# Motor_3.net
KiCad netlist of a schematic drawn in Altium Designer
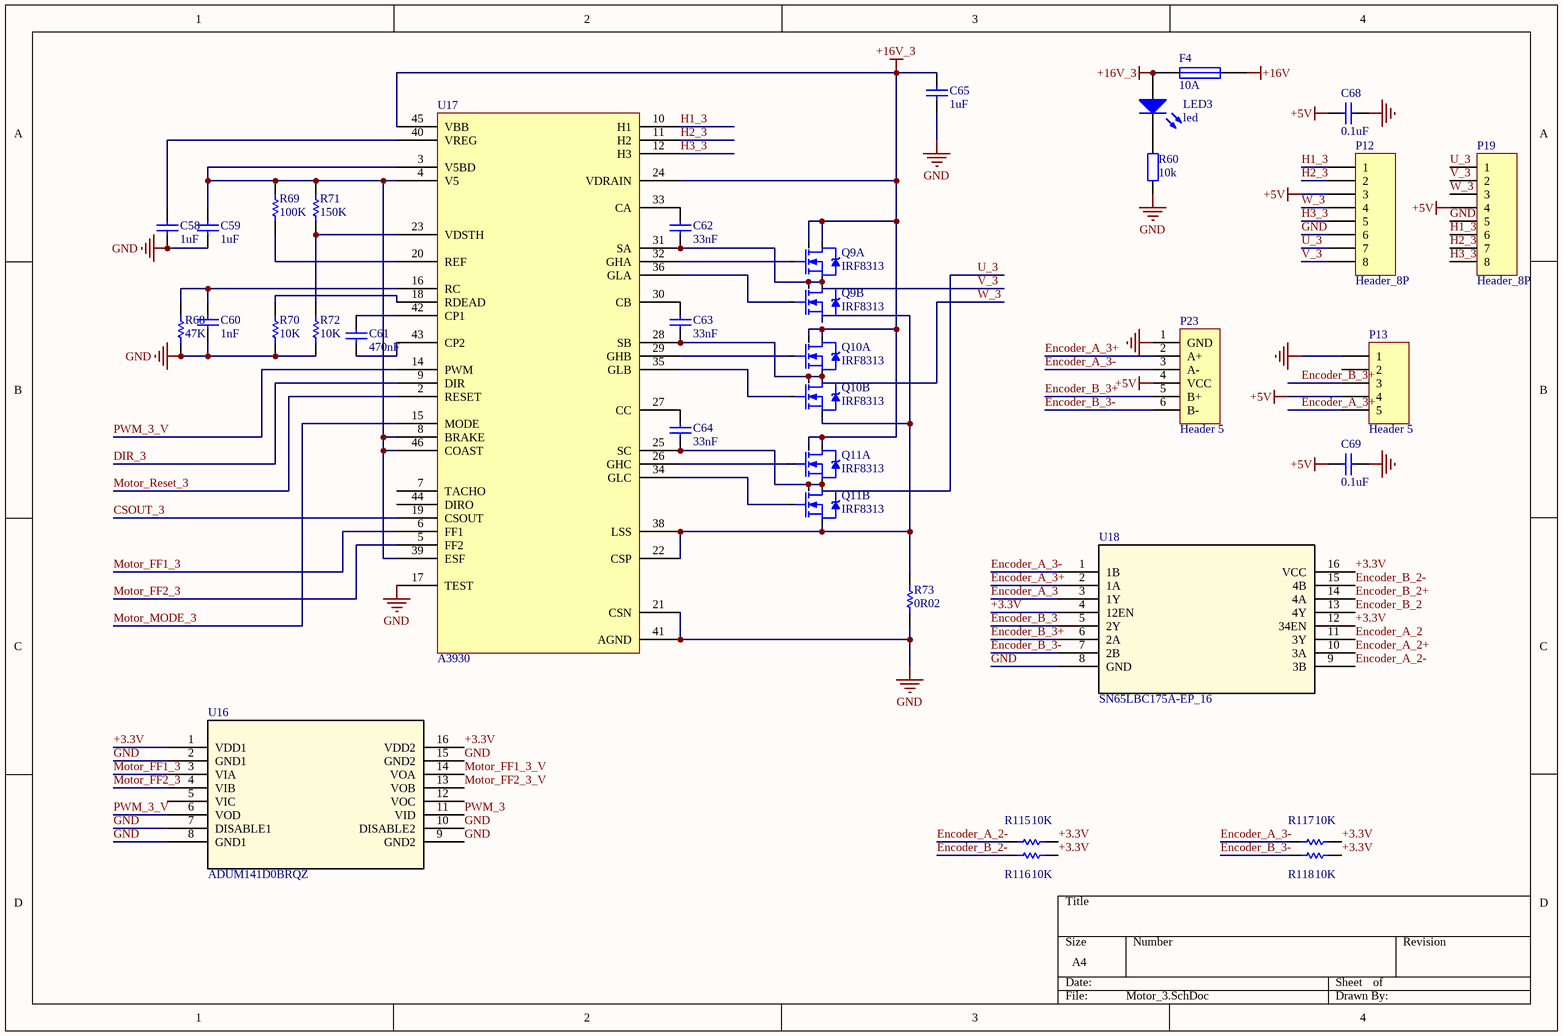
[diagram p0: Motor_3.SchDoc]

(export (version "E")
  (design (tool "Eeschema 10.0.6"))
  (components
    (comp (ref "C58")
      (value "1uF")
      (footprint "0603C")
      (description "Capacitor")
      (fields
        (field (name "MANUFACTURER") "Generic Components")
        (field (name "Comment") "1uf")
        (field (name "PUBLISHER") "Altium Hobart Technology Centre")
      )
      (libsource (lib "hp_2018_03") (part "Cap"))
    )
    (comp (ref "C59")
      (value "1uF")
      (footprint "0603C")
      (description "Capacitor")
      (fields
        (field (name "MANUFACTURER") "Generic Components")
        (field (name "Comment") "1uf")
        (field (name "PUBLISHER") "Altium Hobart Technology Centre")
      )
      (libsource (lib "hp_2018_03") (part "Cap"))
    )
    (comp (ref "C60")
      (value "1nF")
      (footprint "0603C")
      (description "Capacitor")
      (fields
        (field (name "MANUFACTURER") "Generic Components")
        (field (name "Comment") "1nf")
        (field (name "PUBLISHER") "Altium Hobart Technology Centre")
      )
      (libsource (lib "hp_2018_03") (part "Cap"))
    )
    (comp (ref "C61")
      (value "470nF")
      (footprint "0603C")
      (description "Capacitor")
      (fields
        (field (name "MANUFACTURER") "Generic Components")
        (field (name "Comment") "470nf")
        (field (name "PUBLISHER") "Altium Hobart Technology Centre")
      )
      (libsource (lib "hp_2018_03") (part "Cap"))
    )
    (comp (ref "C62")
      (value "33nF")
      (footprint "0603C")
      (description "Capacitor")
      (fields
        (field (name "MANUFACTURER") "Generic Components")
        (field (name "Comment") "33nf")
        (field (name "PUBLISHER") "Altium Hobart Technology Centre")
      )
      (libsource (lib "hp_2018_03") (part "Cap"))
    )
    (comp (ref "C63")
      (value "33nF")
      (footprint "0603C")
      (description "Capacitor")
      (fields
        (field (name "MANUFACTURER") "Generic Components")
        (field (name "Comment") "33nf")
        (field (name "PUBLISHER") "Altium Hobart Technology Centre")
      )
      (libsource (lib "hp_2018_03") (part "Cap"))
    )
    (comp (ref "C64")
      (value "33nF")
      (footprint "0603C")
      (description "Capacitor")
      (fields
        (field (name "MANUFACTURER") "Generic Components")
        (field (name "Comment") "33nf")
        (field (name "PUBLISHER") "Altium Hobart Technology Centre")
      )
      (libsource (lib "hp_2018_03") (part "Cap"))
    )
    (comp (ref "C65")
      (value "1uF")
      (footprint "0603C")
      (description "Capacitor")
      (fields
        (field (name "MANUFACTURER") "Generic Components")
        (field (name "Comment") "1uf")
        (field (name "PUBLISHER") "Altium Hobart Technology Centre")
      )
      (libsource (lib "hp_2018_03") (part "Cap"))
    )
    (comp (ref "C68")
      (value "0.1uF")
      (footprint "0603C")
      (description "Capacitor")
      (fields
        (field (name "MANUFACTURER") "Generic Components")
        (field (name "Comment") "0.1uf")
        (field (name "PUBLISHER") "Altium Hobart Technology Centre")
      )
      (libsource (lib "hp_2018_03") (part "Cap"))
    )
    (comp (ref "C69")
      (value "0.1uF")
      (footprint "0603C")
      (description "Capacitor")
      (fields
        (field (name "MANUFACTURER") "Generic Components")
        (field (name "Comment") "0.1uf")
        (field (name "PUBLISHER") "Altium Hobart Technology Centre")
      )
      (libsource (lib "hp_2018_03") (part "Cap"))
    )
    (comp (ref "F4")
      (value "10A")
      (footprint "Main_Board:FUSE_HEADER")
      (libsource (lib "Integrated_Library2") (part "FUSE"))
    )
    (comp (ref "LED3")
      (value "led")
      (footprint "0603_diode")
      (libsource (lib "Integrated_Library2") (part "led"))
    )
    (comp (ref "P12")
      (value "Header_8P")
      (footprint "8P - WF25122")
      (description "Used for Motor connection in ZJUNlict")
      (libsource (lib "Integrated_Library2") (part "Header_8P"))
    )
    (comp (ref "P13")
      (value "Header 5")
      (footprint "SHDR5")
      (description "Header, 5-Pin")
      (fields (field (name "PUBLISHER") "Altium Limited"))
      (libsource (lib "Miscellaneous Connectors") (part "Header 5"))
    )
    (comp (ref "P19")
      (value "Header_8P")
      (footprint "SHDR8")
      (description "Used for Motor connection in ZJUNlict")
      (libsource (lib "Integrated_Library2") (part "Header_8P"))
    )
    (comp (ref "P23")
      (value "Header 5")
      (footprint "SHDR6")
      (description "Header, 5-Pin")
      (fields (field (name "PUBLISHER") "Altium Limited"))
      (libsource (lib "Main_Board") (part "Header 6"))
    )
    (comp (ref "Q9") (value "IRF8313") (footprint "so-8 bg") (libsource (lib "BLDC") (part "SO-8 IRF8313")))
    (comp (ref "Q10") (value "IRF8313") (footprint "so-8 bg") (libsource (lib "BLDC") (part "SO-8 IRF8313")))
    (comp (ref "Q11") (value "IRF8313") (footprint "so-8 bg") (libsource (lib "BLDC") (part "SO-8 IRF8313")))
    (comp (ref "R60") (value "10k") (footprint "0603") (libsource (lib "Integrated_Library2") (part "res")))
    (comp (ref "R68")
      (value "47K")
      (footprint "0603R")
      (description "Resistor")
      (fields
        (field (name "MANUFACTURER") "Generic Components")
        (field (name "Comment") "47k")
        (field (name "PUBLISHER") "Altium Hobart Technology Centre")
      )
      (libsource (lib "hp_2018_03") (part "Res1"))
    )
    (comp (ref "R69")
      (value "100K")
      (footprint "0603R")
      (description "Resistor")
      (fields
        (field (name "MANUFACTURER") "Generic Components")
        (field (name "Comment") "100k")
        (field (name "PUBLISHER") "Altium Hobart Technology Centre")
      )
      (libsource (lib "hp_2018_03") (part "Res1"))
    )
    (comp (ref "R70")
      (value "10K")
      (footprint "0603R")
      (description "Resistor")
      (fields
        (field (name "MANUFACTURER") "Generic Components")
        (field (name "Comment") "10k")
        (field (name "PUBLISHER") "Altium Hobart Technology Centre")
      )
      (libsource (lib "hp_2018_03") (part "Res1"))
    )
    (comp (ref "R71")
      (value "150K")
      (footprint "0603R")
      (description "Resistor")
      (fields
        (field (name "MANUFACTURER") "Generic Components")
        (field (name "Comment") "100k")
        (field (name "PUBLISHER") "Altium Hobart Technology Centre")
      )
      (libsource (lib "hp_2018_03") (part "Res1"))
    )
    (comp (ref "R72")
      (value "10K")
      (footprint "0603R")
      (description "Resistor")
      (fields
        (field (name "MANUFACTURER") "Generic Components")
        (field (name "Comment") "10k")
        (field (name "PUBLISHER") "Altium Hobart Technology Centre")
      )
      (libsource (lib "hp_2018_03") (part "Res1"))
    )
    (comp (ref "R73")
      (value "0R02")
      (footprint "1206 10A")
      (description "Resistor")
      (fields
        (field (name "MANUFACTURER") "Generic Components")
        (field (name "Comment") "0.02")
        (field (name "PUBLISHER") "Altium Hobart Technology Centre")
      )
      (libsource (lib "hp_2018_03") (part "Res1"))
    )
    (comp (ref "R115")
      (value "10K")
      (footprint "0603R")
      (description "Resistor")
      (fields
        (field (name "MANUFACTURER") "Generic Components")
        (field (name "Comment") "10k")
        (field (name "PUBLISHER") "Altium Hobart Technology Centre")
      )
      (libsource (lib "hp_2018_03") (part "Res1"))
    )
    (comp (ref "R116")
      (value "10K")
      (footprint "0603R")
      (description "Resistor")
      (fields
        (field (name "MANUFACTURER") "Generic Components")
        (field (name "Comment") "10k")
        (field (name "PUBLISHER") "Altium Hobart Technology Centre")
      )
      (libsource (lib "hp_2018_03") (part "Res1"))
    )
    (comp (ref "R117")
      (value "10K")
      (footprint "0603R")
      (description "Resistor")
      (fields
        (field (name "MANUFACTURER") "Generic Components")
        (field (name "Comment") "10k")
        (field (name "PUBLISHER") "Altium Hobart Technology Centre")
      )
      (libsource (lib "hp_2018_03") (part "Res1"))
    )
    (comp (ref "R118")
      (value "10K")
      (footprint "0603R")
      (description "Resistor")
      (fields
        (field (name "MANUFACTURER") "Generic Components")
        (field (name "Comment") "10k")
        (field (name "PUBLISHER") "Altium Hobart Technology Centre")
      )
      (libsource (lib "hp_2018_03") (part "Res1"))
    )
    (comp (ref "U16")
      (value "ADUM141D0BRQZ")
      (footprint "Main_Board:RQ_16")
      (description "Imported")
      (libsource (lib "Main_Board") (part "ADUM141D0BRQZ"))
    )
    (comp (ref "U17") (value "A3930") (footprint "LQFP-48") (libsource (lib "BLDC") (part "LQFP 48")))
    (comp (ref "U18")
      (value "SN65LBC175A-EP_16")
      (footprint "SOP16")
      (description "Quadruple 2-Input Positive-NAND Gates")
      (fields
        (field (name "MANUFACTURER") "Texas Instruments")
        (field (name "GENERIC_PART_NUMBER") "74AC11000")
      )
      (libsource (lib "Main_Board") (part "SN65LBC175A-EP_16"))
    )
  )
  (nets
    (net (code "1") (name "+5V") (class "Default")
      (node (ref "C68") (pin "2") (pinfunction "2_2") (pintype "passive"))
      (node (ref "C69") (pin "2") (pinfunction "2_2") (pintype "passive"))
      (node (ref "P12") (pin "3") (pinfunction "3_3") (pintype "passive"))
      (node (ref "P13") (pin "4") (pinfunction "4_4") (pintype "passive"))
      (node (ref "P19") (pin "4") (pinfunction "4_4") (pintype "passive"))
      (node (ref "P23") (pin "4") (pinfunction "VCC_4") (pintype "passive"))
    )
    (net (code "2") (name "+16V") (class "Default")
      (node (ref "F4") (pin "1") (pinfunction "1_1") (pintype "passive"))
    )
    (net (code "3") (name "+16V_3") (class "Default")
      (node (ref "C65") (pin "2") (pinfunction "2_2") (pintype "passive"))
      (node (ref "F4") (pin "2") (pinfunction "2_2") (pintype "passive"))
      (node (ref "LED3") (pin "1") (pinfunction "A_1") (pintype "passive"))
      (node (ref "Q10") (pin "7") (pinfunction "D2_7") (pintype "passive"))
      (node (ref "Q10") (pin "8") (pinfunction "D2_8") (pintype "passive"))
      (node (ref "Q11") (pin "7") (pinfunction "D2_7") (pintype "passive"))
      (node (ref "Q11") (pin "8") (pinfunction "D2_8") (pintype "passive"))
      (node (ref "Q9") (pin "7") (pinfunction "D2_7") (pintype "passive"))
      (node (ref "Q9") (pin "8") (pinfunction "D2_8") (pintype "passive"))
      (node (ref "U17") (pin "24") (pinfunction "VDRAIN_24") (pintype "passive"))
      (node (ref "U17") (pin "45") (pinfunction "VBB_45") (pintype "passive"))
    )
    (net (code "4") (name "/+3.3V") (class "Default")
      (node (ref "R115") (pin "1") (pinfunction "1_1") (pintype "passive"))
      (node (ref "R116") (pin "1") (pinfunction "1_1") (pintype "passive"))
      (node (ref "R117") (pin "1") (pinfunction "1_1") (pintype "passive"))
      (node (ref "R118") (pin "1") (pinfunction "1_1") (pintype "passive"))
      (node (ref "U16") (pin "1") (pinfunction "VDD1_1") (pintype "passive"))
      (node (ref "U16") (pin "16") (pinfunction "VDD2_16") (pintype "passive"))
      (node (ref "U18") (pin "12") (pinfunction "34EN_12") (pintype "passive"))
      (node (ref "U18") (pin "16") (pinfunction "VCC_16") (pintype "power_in"))
      (node (ref "U18") (pin "4") (pinfunction "12EN_4") (pintype "passive"))
    )
    (net (code "5") (name "/CSOUT_3") (class "Default")
      (node (ref "U17") (pin "19") (pinfunction "CSOUT_19") (pintype "passive"))
    )
    (net (code "6") (name "/DIR_3") (class "Default")
      (node (ref "U17") (pin "9") (pinfunction "DIR_9") (pintype "passive"))
    )
    (net (code "7") (name "/Encoder_A_2") (class "Default")
      (node (ref "U18") (pin "11") (pinfunction "3Y_11") (pintype "passive"))
    )
    (net (code "8") (name "/Encoder_A_2+") (class "Default")
      (node (ref "U18") (pin "10") (pinfunction "3A_10") (pintype "passive"))
    )
    (net (code "9") (name "/Encoder_A_2-") (class "Default")
      (node (ref "R115") (pin "2") (pinfunction "2_2") (pintype "passive"))
      (node (ref "U18") (pin "9") (pinfunction "3B_9") (pintype "passive"))
    )
    (net (code "10") (name "/Encoder_A_3") (class "Default")
      (node (ref "U18") (pin "3") (pinfunction "1Y_3") (pintype "passive"))
    )
    (net (code "11") (name "/Encoder_A_3+") (class "Default")
      (node (ref "P13") (pin "5") (pinfunction "5_5") (pintype "passive"))
      (node (ref "P23") (pin "2") (pinfunction "A+_2") (pintype "passive"))
      (node (ref "U18") (pin "2") (pinfunction "1A_2") (pintype "passive"))
    )
    (net (code "12") (name "/Encoder_A_3-") (class "Default")
      (node (ref "P23") (pin "3") (pinfunction "A-_3") (pintype "passive"))
      (node (ref "R117") (pin "2") (pinfunction "2_2") (pintype "passive"))
      (node (ref "U18") (pin "1") (pinfunction "1B_1") (pintype "passive"))
    )
    (net (code "13") (name "/Encoder_B_2") (class "Default")
      (node (ref "U18") (pin "13") (pinfunction "4Y_13") (pintype "passive"))
    )
    (net (code "14") (name "/Encoder_B_2+") (class "Default")
      (node (ref "U18") (pin "14") (pinfunction "4A_14") (pintype "passive"))
    )
    (net (code "15") (name "/Encoder_B_2-") (class "Default")
      (node (ref "R116") (pin "2") (pinfunction "2_2") (pintype "passive"))
      (node (ref "U18") (pin "15") (pinfunction "4B_15") (pintype "passive"))
    )
    (net (code "16") (name "/Encoder_B_3") (class "Default")
      (node (ref "U18") (pin "5") (pinfunction "2Y_5") (pintype "passive"))
    )
    (net (code "17") (name "/Encoder_B_3+") (class "Default")
      (node (ref "P13") (pin "3") (pinfunction "3_3") (pintype "passive"))
      (node (ref "P23") (pin "5") (pinfunction "B+_5") (pintype "passive"))
      (node (ref "U18") (pin "6") (pinfunction "2A_6") (pintype "passive"))
    )
    (net (code "18") (name "/Encoder_B_3-") (class "Default")
      (node (ref "P23") (pin "6") (pinfunction "B-_6") (pintype "passive"))
      (node (ref "R118") (pin "2") (pinfunction "2_2") (pintype "passive"))
      (node (ref "U18") (pin "7") (pinfunction "2B_7") (pintype "passive"))
    )
    (net (code "19") (name "/H1_3") (class "Default")
      (node (ref "P12") (pin "1") (pinfunction "1_1") (pintype "passive"))
      (node (ref "P19") (pin "6") (pinfunction "6_6") (pintype "passive"))
      (node (ref "U17") (pin "10") (pinfunction "H1_10") (pintype "passive"))
    )
    (net (code "20") (name "/H2_3") (class "Default")
      (node (ref "P12") (pin "2") (pinfunction "2_2") (pintype "passive"))
      (node (ref "P19") (pin "7") (pinfunction "7_7") (pintype "passive"))
      (node (ref "U17") (pin "11") (pinfunction "H2_11") (pintype "passive"))
    )
    (net (code "21") (name "/H3_3") (class "Default")
      (node (ref "P12") (pin "5") (pinfunction "5_5") (pintype "passive"))
      (node (ref "P19") (pin "8") (pinfunction "8_8") (pintype "passive"))
      (node (ref "U17") (pin "12") (pinfunction "H3_12") (pintype "passive"))
    )
    (net (code "22") (name "/Motor_FF1_3") (class "Default")
      (node (ref "U16") (pin "3") (pinfunction "VIA_3") (pintype "passive"))
      (node (ref "U17") (pin "6") (pinfunction "FF1_6") (pintype "passive"))
    )
    (net (code "23") (name "/Motor_FF1_3_V") (class "Default")
      (node (ref "U16") (pin "14") (pinfunction "VOA_14") (pintype "passive"))
    )
    (net (code "24") (name "/Motor_FF2_3") (class "Default")
      (node (ref "U16") (pin "4") (pinfunction "VIB_4") (pintype "passive"))
      (node (ref "U17") (pin "5") (pinfunction "FF2_5") (pintype "passive"))
    )
    (net (code "25") (name "/Motor_FF2_3_V") (class "Default")
      (node (ref "U16") (pin "13") (pinfunction "VOB_13") (pintype "passive"))
    )
    (net (code "26") (name "/Motor_MODE_3") (class "Default")
      (node (ref "U17") (pin "15") (pinfunction "MODE_15") (pintype "passive"))
    )
    (net (code "27") (name "/Motor_Reset_3") (class "Default")
      (node (ref "U17") (pin "2") (pinfunction "RESET_2") (pintype "passive"))
    )
    (net (code "28") (name "/PWM_3") (class "Default")
      (node (ref "U16") (pin "11") (pinfunction "VID_11") (pintype "passive"))
    )
    (net (code "29") (name "/PWM_3_V") (class "Default")
      (node (ref "U16") (pin "6") (pinfunction "VOD_6") (pintype "passive"))
      (node (ref "U17") (pin "14") (pinfunction "PWM_14") (pintype "passive"))
    )
    (net (code "30") (name "/U_3") (class "Default")
      (node (ref "C64") (pin "1") (pinfunction "1_1") (pintype "passive"))
      (node (ref "P12") (pin "7") (pinfunction "7_7") (pintype "passive"))
      (node (ref "P19") (pin "1") (pinfunction "1_1") (pintype "passive"))
      (node (ref "Q11") (pin "1") (pinfunction "S2_1") (pintype "passive"))
      (node (ref "Q11") (pin "5") (pinfunction "D1_5") (pintype "passive"))
      (node (ref "Q11") (pin "6") (pinfunction "D1_6") (pintype "passive"))
      (node (ref "U17") (pin "25") (pinfunction "SC_25") (pintype "passive"))
    )
    (net (code "31") (name "/V_3") (class "Default")
      (node (ref "C62") (pin "1") (pinfunction "1_1") (pintype "passive"))
      (node (ref "P12") (pin "8") (pinfunction "8_8") (pintype "passive"))
      (node (ref "P19") (pin "2") (pinfunction "2_2") (pintype "passive"))
      (node (ref "Q9") (pin "1") (pinfunction "S2_1") (pintype "passive"))
      (node (ref "Q9") (pin "5") (pinfunction "D1_5") (pintype "passive"))
      (node (ref "Q9") (pin "6") (pinfunction "D1_6") (pintype "passive"))
      (node (ref "U17") (pin "31") (pinfunction "SA_31") (pintype "passive"))
    )
    (net (code "32") (name "/W_3") (class "Default")
      (node (ref "C63") (pin "1") (pinfunction "1_1") (pintype "passive"))
      (node (ref "P12") (pin "4") (pinfunction "4_4") (pintype "passive"))
      (node (ref "P19") (pin "3") (pinfunction "3_3") (pintype "passive"))
      (node (ref "Q10") (pin "1") (pinfunction "S2_1") (pintype "passive"))
      (node (ref "Q10") (pin "5") (pinfunction "D1_5") (pintype "passive"))
      (node (ref "Q10") (pin "6") (pinfunction "D1_6") (pintype "passive"))
      (node (ref "U17") (pin "28") (pinfunction "SB_28") (pintype "passive"))
    )
    (net (code "33") (name "GND") (class "Default")
      (node (ref "C58") (pin "1") (pinfunction "1_1") (pintype "passive"))
      (node (ref "C59") (pin "1") (pinfunction "1_1") (pintype "passive"))
      (node (ref "C60") (pin "1") (pinfunction "1_1") (pintype "passive"))
      (node (ref "C65") (pin "1") (pinfunction "1_1") (pintype "passive"))
      (node (ref "C68") (pin "1") (pinfunction "1_1") (pintype "passive"))
      (node (ref "C69") (pin "1") (pinfunction "1_1") (pintype "passive"))
      (node (ref "P12") (pin "6") (pinfunction "6_6") (pintype "passive"))
      (node (ref "P13") (pin "1") (pinfunction "1_1") (pintype "passive"))
      (node (ref "P19") (pin "5") (pinfunction "5_5") (pintype "passive"))
      (node (ref "P23") (pin "1") (pinfunction "GND_1") (pintype "passive"))
      (node (ref "R60") (pin "1") (pinfunction "1_1") (pintype "passive"))
      (node (ref "R68") (pin "1") (pinfunction "1_1") (pintype "passive"))
      (node (ref "R70") (pin "1") (pinfunction "1_1") (pintype "passive"))
      (node (ref "R72") (pin "1") (pinfunction "1_1") (pintype "passive"))
      (node (ref "R73") (pin "1") (pinfunction "1_1") (pintype "passive"))
      (node (ref "U16") (pin "10") (pinfunction "DISABLE2_10") (pintype "passive"))
      (node (ref "U16") (pin "15") (pinfunction "GND2_15") (pintype "passive"))
      (node (ref "U16") (pin "2") (pinfunction "GND1_2") (pintype "passive"))
      (node (ref "U16") (pin "7") (pinfunction "DISABLE1_7") (pintype "passive"))
      (node (ref "U16") (pin "8") (pinfunction "GND1_8") (pintype "passive"))
      (node (ref "U16") (pin "9") (pinfunction "GND2_9") (pintype "passive"))
      (node (ref "U17") (pin "17") (pinfunction "TEST_17") (pintype "passive"))
      (node (ref "U17") (pin "21") (pinfunction "CSN_21") (pintype "passive"))
      (node (ref "U17") (pin "41") (pinfunction "AGND_41") (pintype "passive"))
      (node (ref "U18") (pin "8") (pinfunction "GND_8") (pintype "passive"))
    )
    (net (code "34") (name "Net-(LED3-K)") (class "Default")
      (node (ref "LED3") (pin "2") (pinfunction "K_2") (pintype "passive"))
      (node (ref "R60") (pin "2") (pinfunction "2_2") (pintype "passive"))
    )
    (net (code "35") (name "Net-(Q9A-G2)") (class "Default")
      (node (ref "Q9") (pin "2") (pinfunction "G2_2") (pintype "passive"))
      (node (ref "U17") (pin "32") (pinfunction "GHA_32") (pintype "passive"))
    )
    (net (code "36") (name "Net-(Q9B-G1)") (class "Default")
      (node (ref "Q9") (pin "4") (pinfunction "G1_4") (pintype "passive"))
      (node (ref "U17") (pin "36") (pinfunction "GLA_36") (pintype "passive"))
    )
    (net (code "37") (name "Net-(Q10A-G2)") (class "Default")
      (node (ref "Q10") (pin "2") (pinfunction "G2_2") (pintype "passive"))
      (node (ref "U17") (pin "29") (pinfunction "GHB_29") (pintype "passive"))
    )
    (net (code "38") (name "Net-(Q10B-G1)") (class "Default")
      (node (ref "Q10") (pin "4") (pinfunction "G1_4") (pintype "passive"))
      (node (ref "U17") (pin "35") (pinfunction "GLB_35") (pintype "passive"))
    )
    (net (code "39") (name "Net-(Q10B-S1)") (class "Default")
      (node (ref "Q10") (pin "3") (pinfunction "S1_3") (pintype "passive"))
      (node (ref "Q11") (pin "3") (pinfunction "S1_3") (pintype "passive"))
      (node (ref "Q9") (pin "3") (pinfunction "S1_3") (pintype "passive"))
      (node (ref "R73") (pin "2") (pinfunction "2_2") (pintype "passive"))
      (node (ref "U17") (pin "22") (pinfunction "CSP_22") (pintype "passive"))
      (node (ref "U17") (pin "38") (pinfunction "LSS_38") (pintype "passive"))
    )
    (net (code "40") (name "Net-(Q11A-G2)") (class "Default")
      (node (ref "Q11") (pin "2") (pinfunction "G2_2") (pintype "passive"))
      (node (ref "U17") (pin "26") (pinfunction "GHC_26") (pintype "passive"))
    )
    (net (code "41") (name "Net-(Q11B-G1)") (class "Default")
      (node (ref "Q11") (pin "4") (pinfunction "G1_4") (pintype "passive"))
      (node (ref "U17") (pin "34") (pinfunction "GLC_34") (pintype "passive"))
    )
    (net (code "42") (name "Net-(U17-BRAKE)") (class "Default")
      (node (ref "C59") (pin "2") (pinfunction "2_2") (pintype "passive"))
      (node (ref "R69") (pin "2") (pinfunction "2_2") (pintype "passive"))
      (node (ref "R71") (pin "2") (pinfunction "2_2") (pintype "passive"))
      (node (ref "U17") (pin "3") (pinfunction "V5BD_3") (pintype "passive"))
      (node (ref "U17") (pin "39") (pinfunction "ESF_39") (pintype "passive"))
      (node (ref "U17") (pin "4") (pinfunction "V5_4") (pintype "passive"))
      (node (ref "U17") (pin "46") (pinfunction "COAST_46") (pintype "passive"))
      (node (ref "U17") (pin "8") (pinfunction "BRAKE_8") (pintype "passive"))
    )
    (net (code "43") (name "Net-(U17-CA)") (class "Default")
      (node (ref "C62") (pin "2") (pinfunction "2_2") (pintype "passive"))
      (node (ref "U17") (pin "33") (pinfunction "CA_33") (pintype "passive"))
    )
    (net (code "44") (name "Net-(U17-CB)") (class "Default")
      (node (ref "C63") (pin "2") (pinfunction "2_2") (pintype "passive"))
      (node (ref "U17") (pin "30") (pinfunction "CB_30") (pintype "passive"))
    )
    (net (code "45") (name "Net-(U17-CC)") (class "Default")
      (node (ref "C64") (pin "2") (pinfunction "2_2") (pintype "passive"))
      (node (ref "U17") (pin "27") (pinfunction "CC_27") (pintype "passive"))
    )
    (net (code "46") (name "Net-(U17-CP1)") (class "Default")
      (node (ref "C61") (pin "2") (pinfunction "2_2") (pintype "passive"))
      (node (ref "U17") (pin "42") (pinfunction "CP1_42") (pintype "passive"))
    )
    (net (code "47") (name "Net-(U17-CP2)") (class "Default")
      (node (ref "C61") (pin "1") (pinfunction "1_1") (pintype "passive"))
      (node (ref "U17") (pin "43") (pinfunction "CP2_43") (pintype "passive"))
    )
    (net (code "48") (name "Net-(U17-RC)") (class "Default")
      (node (ref "C60") (pin "2") (pinfunction "2_2") (pintype "passive"))
      (node (ref "R68") (pin "2") (pinfunction "2_2") (pintype "passive"))
      (node (ref "U17") (pin "16") (pinfunction "RC_16") (pintype "passive"))
    )
    (net (code "49") (name "Net-(U17-RDEAD)") (class "Default")
      (node (ref "R70") (pin "2") (pinfunction "2_2") (pintype "passive"))
      (node (ref "U17") (pin "18") (pinfunction "RDEAD_18") (pintype "passive"))
    )
    (net (code "50") (name "Net-(U17-REF)") (class "Default")
      (node (ref "R69") (pin "1") (pinfunction "1_1") (pintype "passive"))
      (node (ref "U17") (pin "20") (pinfunction "REF_20") (pintype "passive"))
    )
    (net (code "51") (name "Net-(U17-VDSTH)") (class "Default")
      (node (ref "R71") (pin "1") (pinfunction "1_1") (pintype "passive"))
      (node (ref "R72") (pin "2") (pinfunction "2_2") (pintype "passive"))
      (node (ref "U17") (pin "23") (pinfunction "VDSTH_23") (pintype "passive"))
    )
    (net (code "52") (name "Net-(U17-VREG)") (class "Default")
      (node (ref "C58") (pin "2") (pinfunction "2_2") (pintype "passive"))
      (node (ref "U17") (pin "40") (pinfunction "VREG_40") (pintype "passive"))
    )
    (net (code "53") (name "unconnected-(P13-Pad2)") (class "Default")
      (node (ref "P13") (pin "2") (pinfunction "2_2") (pintype "passive"))
    )
    (net (code "54") (name "unconnected-(U16-VIC-Pad5)") (class "Default")
      (node (ref "U16") (pin "5") (pinfunction "VIC_5") (pintype "passive"))
    )
    (net (code "55") (name "unconnected-(U16-VOC-Pad12)") (class "Default")
      (node (ref "U16") (pin "12") (pinfunction "VOC_12") (pintype "passive"))
    )
    (net (code "56") (name "unconnected-(U17-DIRO-Pad44)") (class "Default")
      (node (ref "U17") (pin "44") (pinfunction "DIRO_44") (pintype "passive"))
    )
    (net (code "57") (name "unconnected-(U17-TACHO-Pad7)") (class "Default")
      (node (ref "U17") (pin "7") (pinfunction "TACHO_7") (pintype "passive"))
    )
  )
)
